# pico-v3.net
KiCad netlist of a schematic drawn in EAGLE
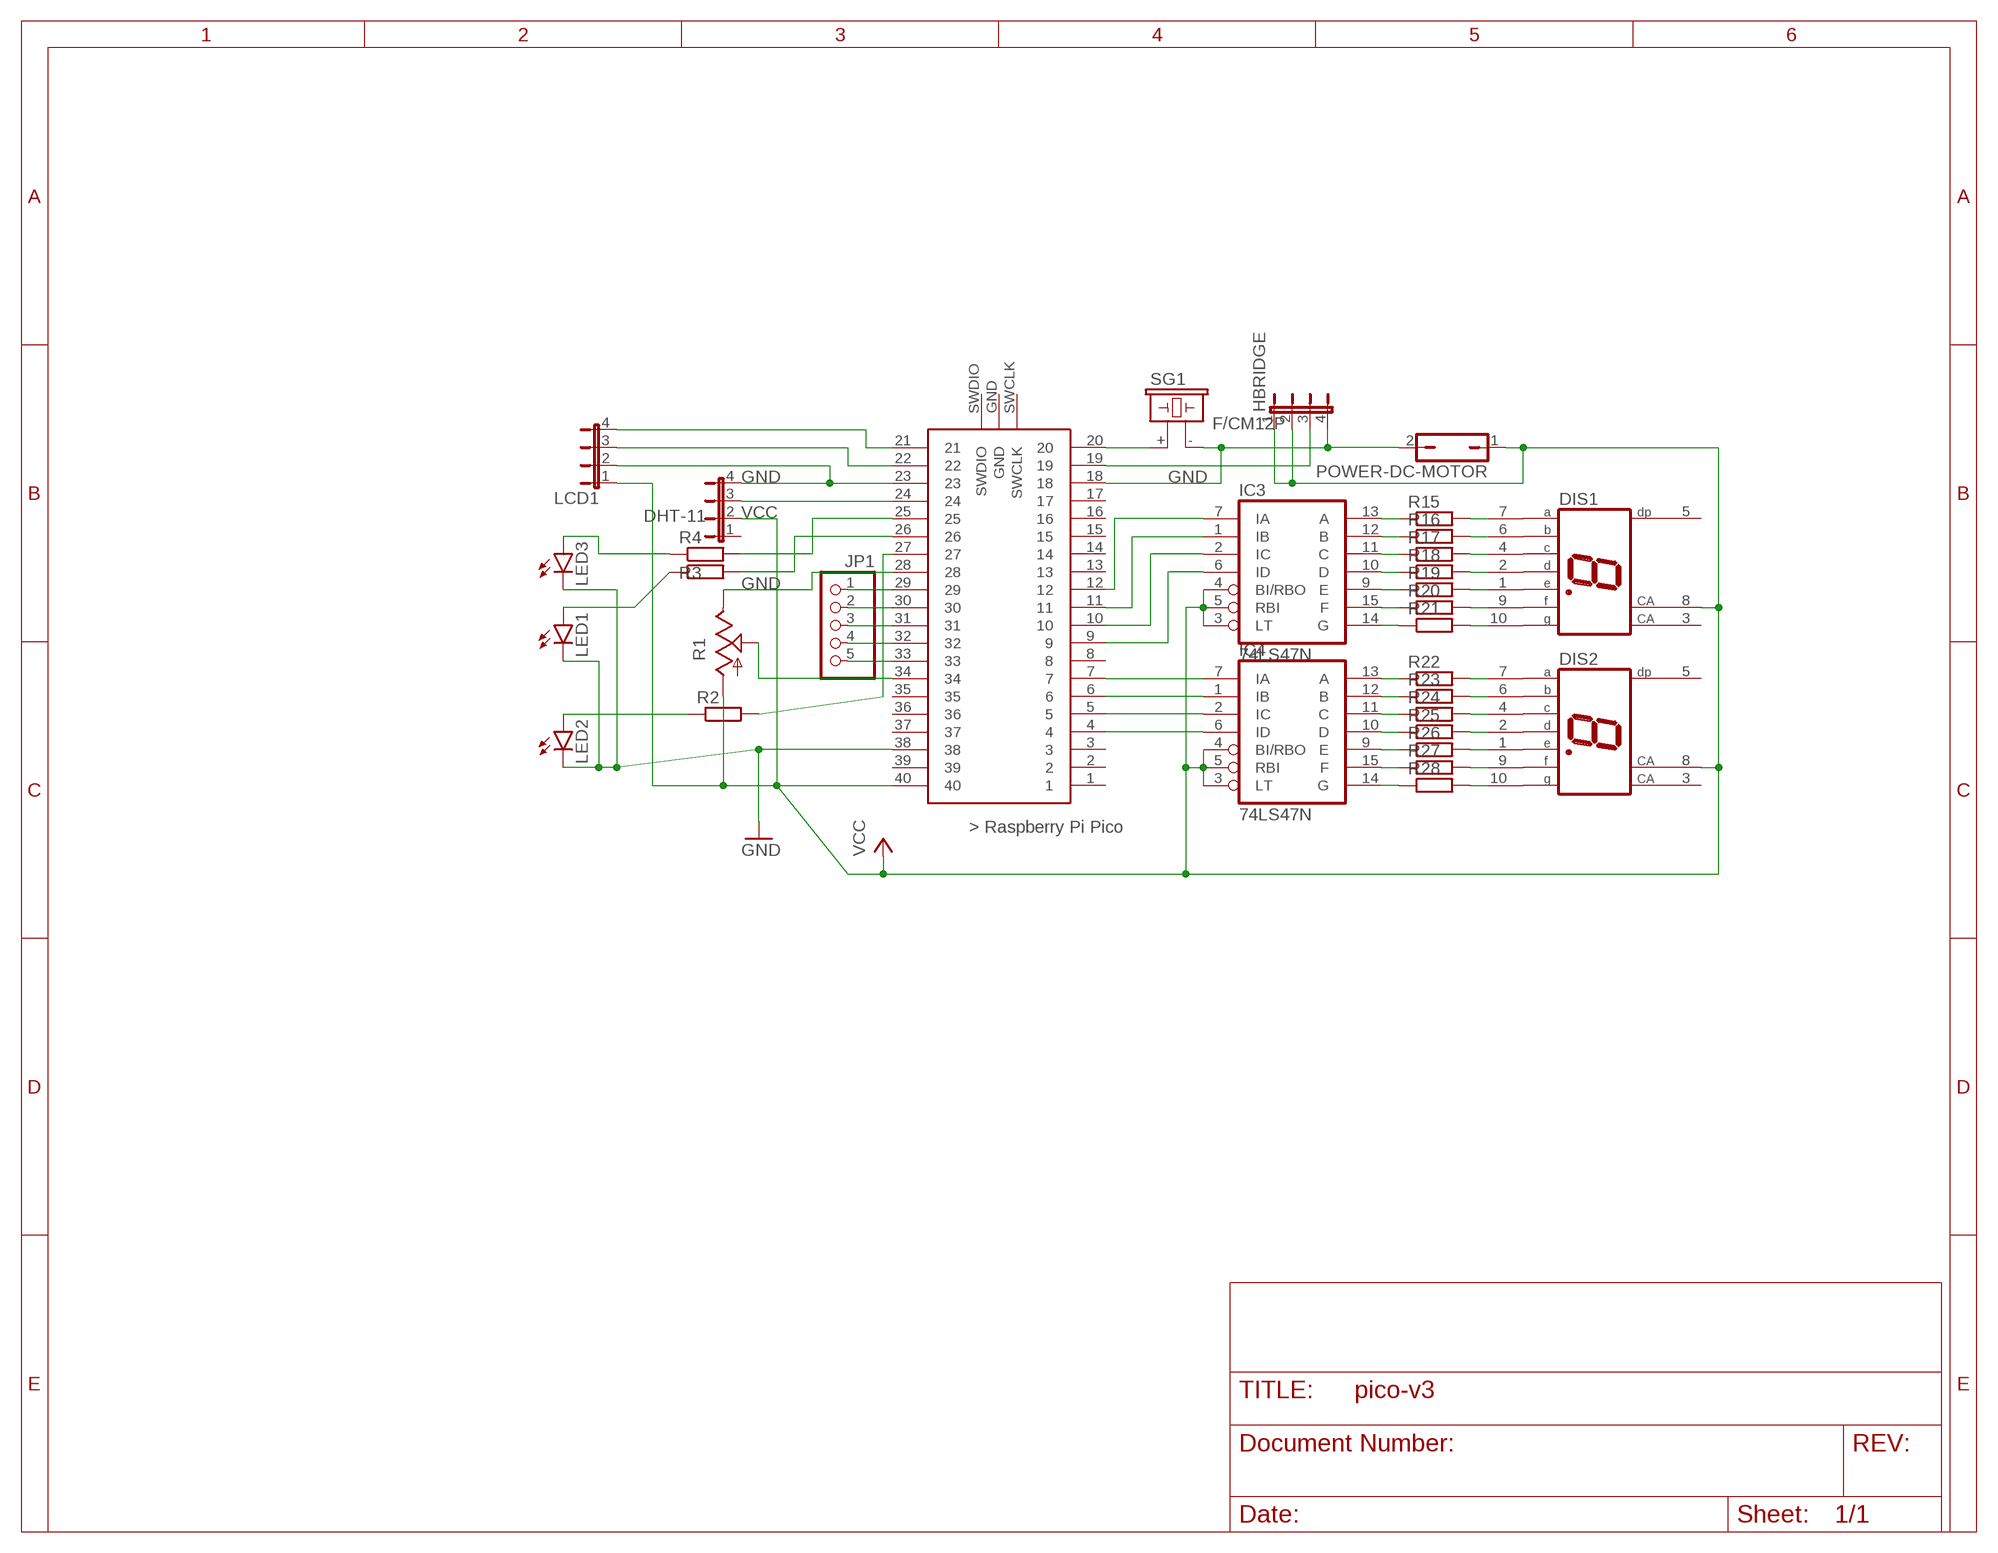
[diagram p0: schematic, sheet 1]

(export (version "E")
  (design (tool "Eeschema 10.0.6"))
  (components
    (comp (ref "DHT-11")
      (value "JP4E")
      (footprint "eagle-import:JP4")
      (libsource (lib "eagle-import") (part "JP4E"))
    )
    (comp (ref "DIS1")
      (value "HD-H101")
      (footprint "eagle-import:HDSP-M")
      (libsource (lib "eagle-import") (part "HD-H101"))
    )
    (comp (ref "DIS2")
      (value "HD-H101")
      (footprint "eagle-import:HDSP-M")
      (libsource (lib "eagle-import") (part "HD-H101"))
    )
    (comp (ref "HBRIDGE")
      (value "JP4E")
      (footprint "eagle-import:JP4")
      (libsource (lib "eagle-import") (part "JP4E"))
    )
    (comp (ref "IC3")
      (value "74LS47N")
      (footprint "eagle-import:DIL16")
      (libsource (lib "eagle-import") (part "7447NLS"))
    )
    (comp (ref "IC4")
      (value "74LS47N")
      (footprint "eagle-import:DIL16")
      (libsource (lib "eagle-import") (part "7447NLS"))
    )
    (comp (ref "JP1")
      (value "PINHD-1X5")
      (footprint "eagle-import:1X05")
      (libsource (lib "eagle-import") (part "PINHD-1X5"))
    )
    (comp (ref "LCD1")
      (value "JP4E")
      (footprint "eagle-import:JP4")
      (libsource (lib "eagle-import") (part "JP4E"))
    )
    (comp (ref "LED1")
      (value "LED5MM")
      (footprint "eagle-import:LED5MM")
      (libsource (lib "eagle-import") (part "LED5MM"))
    )
    (comp (ref "LED2")
      (value "LED5MM")
      (footprint "eagle-import:LED5MM")
      (libsource (lib "eagle-import") (part "LED5MM"))
    )
    (comp (ref "LED3")
      (value "LED5MM")
      (footprint "eagle-import:LED5MM")
      (libsource (lib "eagle-import") (part "LED5MM"))
    )
    (comp (ref "POWER-DC-MOTOR")
      (value "JP1Q")
      (footprint "eagle-import:JP1")
      (libsource (lib "eagle-import") (part "JP1Q"))
    )
    (comp (ref "R1")
      (value "TRIM_US-CA6V")
      (footprint "eagle-import:CA6V")
      (libsource (lib "eagle-import") (part "TRIM_US-CA6V"))
    )
    (comp (ref "R2")
      (value "R-EU_0207/10")
      (footprint "eagle-import:0207_10")
      (libsource (lib "eagle-import") (part "R-EU_0207/10"))
    )
    (comp (ref "R3")
      (value "R-EU_0207/10")
      (footprint "eagle-import:0207_10")
      (libsource (lib "eagle-import") (part "R-EU_0207/10"))
    )
    (comp (ref "R4")
      (value "R-EU_0207/10")
      (footprint "eagle-import:0207_10")
      (libsource (lib "eagle-import") (part "R-EU_0207/10"))
    )
    (comp (ref "R15")
      (value "R-EU_0207/12")
      (footprint "eagle-import:0207_12")
      (libsource (lib "eagle-import") (part "R-EU_0207/12"))
    )
    (comp (ref "R16")
      (value "R-EU_0207/12")
      (footprint "eagle-import:0207_12")
      (libsource (lib "eagle-import") (part "R-EU_0207/12"))
    )
    (comp (ref "R17")
      (value "R-EU_0207/12")
      (footprint "eagle-import:0207_12")
      (libsource (lib "eagle-import") (part "R-EU_0207/12"))
    )
    (comp (ref "R18")
      (value "R-EU_0207/12")
      (footprint "eagle-import:0207_12")
      (libsource (lib "eagle-import") (part "R-EU_0207/12"))
    )
    (comp (ref "R19")
      (value "R-EU_0207/12")
      (footprint "eagle-import:0207_12")
      (libsource (lib "eagle-import") (part "R-EU_0207/12"))
    )
    (comp (ref "R20")
      (value "R-EU_0207/12")
      (footprint "eagle-import:0207_12")
      (libsource (lib "eagle-import") (part "R-EU_0207/12"))
    )
    (comp (ref "R21")
      (value "R-EU_0207/12")
      (footprint "eagle-import:0207_12")
      (libsource (lib "eagle-import") (part "R-EU_0207/12"))
    )
    (comp (ref "R22")
      (value "R-EU_0207/12")
      (footprint "eagle-import:0207_12")
      (libsource (lib "eagle-import") (part "R-EU_0207/12"))
    )
    (comp (ref "R23")
      (value "R-EU_0207/12")
      (footprint "eagle-import:0207_12")
      (libsource (lib "eagle-import") (part "R-EU_0207/12"))
    )
    (comp (ref "R24")
      (value "R-EU_0207/12")
      (footprint "eagle-import:0207_12")
      (libsource (lib "eagle-import") (part "R-EU_0207/12"))
    )
    (comp (ref "R25")
      (value "R-EU_0207/12")
      (footprint "eagle-import:0207_12")
      (libsource (lib "eagle-import") (part "R-EU_0207/12"))
    )
    (comp (ref "R26")
      (value "R-EU_0207/12")
      (footprint "eagle-import:0207_12")
      (libsource (lib "eagle-import") (part "R-EU_0207/12"))
    )
    (comp (ref "R27")
      (value "R-EU_0207/12")
      (footprint "eagle-import:0207_12")
      (libsource (lib "eagle-import") (part "R-EU_0207/12"))
    )
    (comp (ref "R28")
      (value "R-EU_0207/12")
      (footprint "eagle-import:0207_12")
      (libsource (lib "eagle-import") (part "R-EU_0207/12"))
    )
    (comp (ref "SG1")
      (value "F/CM12P")
      (footprint "eagle-import:F_CM12P")
      (libsource (lib "eagle-import") (part "F/CM12P"))
    )
    (comp (ref "U$1")
      (value "RASPBERRY-PI-PICO_TH")
      (footprint "eagle-import:FT_RASPBERRY-PI-PICO_TH")
      (libsource (lib "eagle-import") (part "RASPBERRY-PI-PICO_TH"))
    )
  )
  (nets
    (net (code "1") (name "GND") (class "Default")
      (node (ref "DHT-11") (pin "4") (pinfunction "4_4") (pintype "passive"))
      (node (ref "HBRIDGE") (pin "4") (pinfunction "4_4") (pintype "passive"))
      (node (ref "LCD1") (pin "2") (pinfunction "2_2") (pintype "passive"))
      (node (ref "LED1") (pin "K") (pinfunction "C_K") (pintype "passive"))
      (node (ref "LED2") (pin "K") (pinfunction "C_K") (pintype "passive"))
      (node (ref "LED3") (pin "K") (pinfunction "C_K") (pintype "passive"))
      (node (ref "POWER-DC-MOTOR") (pin "2") (pinfunction "2_2") (pintype "passive"))
      (node (ref "R1") (pin "E") (pinfunction "E_E") (pintype "passive"))
      (node (ref "SG1") (pin "-") (pinfunction "2_-") (pintype "passive"))
      (node (ref "U$1") (pin "18") (pinfunction "18_18") (pintype "bidirectional"))
      (node (ref "U$1") (pin "23") (pinfunction "23_23") (pintype "bidirectional"))
      (node (ref "U$1") (pin "28") (pinfunction "28_28") (pintype "bidirectional"))
      (node (ref "U$1") (pin "38") (pinfunction "38_38") (pintype "bidirectional"))
    )
    (net (code "2") (name "Net-(DHT-11-Pad3)") (class "Default")
      (node (ref "DHT-11") (pin "3") (pinfunction "3_3") (pintype "passive"))
      (node (ref "U$1") (pin "24") (pinfunction "24_24") (pintype "bidirectional"))
    )
    (net (code "3") (name "Net-(DIS1-A)") (class "Default")
      (node (ref "DIS1") (pin "7") (pinfunction "A_7") (pintype "passive"))
      (node (ref "R15") (pin "2") (pinfunction "2_2") (pintype "passive"))
    )
    (net (code "4") (name "Net-(DIS1-B)") (class "Default")
      (node (ref "DIS1") (pin "6") (pinfunction "B_6") (pintype "passive"))
      (node (ref "R16") (pin "2") (pinfunction "2_2") (pintype "passive"))
    )
    (net (code "5") (name "Net-(DIS1-C)") (class "Default")
      (node (ref "DIS1") (pin "4") (pinfunction "C_4") (pintype "passive"))
      (node (ref "R17") (pin "2") (pinfunction "2_2") (pintype "passive"))
    )
    (net (code "6") (name "Net-(DIS1-D)") (class "Default")
      (node (ref "DIS1") (pin "2") (pinfunction "D_2") (pintype "passive"))
      (node (ref "R18") (pin "2") (pinfunction "2_2") (pintype "passive"))
    )
    (net (code "7") (name "Net-(DIS1-E)") (class "Default")
      (node (ref "DIS1") (pin "1") (pinfunction "E_1") (pintype "passive"))
      (node (ref "R19") (pin "2") (pinfunction "2_2") (pintype "passive"))
    )
    (net (code "8") (name "Net-(DIS1-F)") (class "Default")
      (node (ref "DIS1") (pin "9") (pinfunction "F_9") (pintype "passive"))
      (node (ref "R20") (pin "2") (pinfunction "2_2") (pintype "passive"))
    )
    (net (code "9") (name "Net-(DIS1-G)") (class "Default")
      (node (ref "DIS1") (pin "10") (pinfunction "G_10") (pintype "passive"))
      (node (ref "R21") (pin "2") (pinfunction "2_2") (pintype "passive"))
    )
    (net (code "10") (name "Net-(DIS2-A)") (class "Default")
      (node (ref "DIS2") (pin "7") (pinfunction "A_7") (pintype "passive"))
      (node (ref "R22") (pin "2") (pinfunction "2_2") (pintype "passive"))
    )
    (net (code "11") (name "Net-(DIS2-B)") (class "Default")
      (node (ref "DIS2") (pin "6") (pinfunction "B_6") (pintype "passive"))
      (node (ref "R23") (pin "2") (pinfunction "2_2") (pintype "passive"))
    )
    (net (code "12") (name "Net-(DIS2-C)") (class "Default")
      (node (ref "DIS2") (pin "4") (pinfunction "C_4") (pintype "passive"))
      (node (ref "R24") (pin "2") (pinfunction "2_2") (pintype "passive"))
    )
    (net (code "13") (name "Net-(DIS2-D)") (class "Default")
      (node (ref "DIS2") (pin "2") (pinfunction "D_2") (pintype "passive"))
      (node (ref "R25") (pin "2") (pinfunction "2_2") (pintype "passive"))
    )
    (net (code "14") (name "Net-(DIS2-E)") (class "Default")
      (node (ref "DIS2") (pin "1") (pinfunction "E_1") (pintype "passive"))
      (node (ref "R26") (pin "2") (pinfunction "2_2") (pintype "passive"))
    )
    (net (code "15") (name "Net-(DIS2-F)") (class "Default")
      (node (ref "DIS2") (pin "9") (pinfunction "F_9") (pintype "passive"))
      (node (ref "R27") (pin "2") (pinfunction "2_2") (pintype "passive"))
    )
    (net (code "16") (name "Net-(DIS2-G)") (class "Default")
      (node (ref "DIS2") (pin "10") (pinfunction "G_10") (pintype "passive"))
      (node (ref "R28") (pin "2") (pinfunction "2_2") (pintype "passive"))
    )
    (net (code "17") (name "Net-(HBRIDGE-Pad3)") (class "Default")
      (node (ref "HBRIDGE") (pin "3") (pinfunction "3_3") (pintype "passive"))
      (node (ref "U$1") (pin "19") (pinfunction "19_19") (pintype "bidirectional"))
    )
    (net (code "18") (name "Net-(IC3A-A)") (class "Default")
      (node (ref "IC3") (pin "13") (pinfunction "A_13") (pintype "output"))
      (node (ref "R15") (pin "1") (pinfunction "1_1") (pintype "passive"))
    )
    (net (code "19") (name "Net-(IC3A-B)") (class "Default")
      (node (ref "IC3") (pin "12") (pinfunction "B_12") (pintype "output"))
      (node (ref "R16") (pin "1") (pinfunction "1_1") (pintype "passive"))
    )
    (net (code "20") (name "Net-(IC3A-C)") (class "Default")
      (node (ref "IC3") (pin "11") (pinfunction "C_11") (pintype "output"))
      (node (ref "R17") (pin "1") (pinfunction "1_1") (pintype "passive"))
    )
    (net (code "21") (name "Net-(IC3A-D)") (class "Default")
      (node (ref "IC3") (pin "10") (pinfunction "D_10") (pintype "output"))
      (node (ref "R18") (pin "1") (pinfunction "1_1") (pintype "passive"))
    )
    (net (code "22") (name "Net-(IC3A-E)") (class "Default")
      (node (ref "IC3") (pin "9") (pinfunction "E_9") (pintype "output"))
      (node (ref "R19") (pin "1") (pinfunction "1_1") (pintype "passive"))
    )
    (net (code "23") (name "Net-(IC3A-F)") (class "Default")
      (node (ref "IC3") (pin "15") (pinfunction "F_15") (pintype "output"))
      (node (ref "R20") (pin "1") (pinfunction "1_1") (pintype "passive"))
    )
    (net (code "24") (name "Net-(IC3A-G)") (class "Default")
      (node (ref "IC3") (pin "14") (pinfunction "G_14") (pintype "output"))
      (node (ref "R21") (pin "1") (pinfunction "1_1") (pintype "passive"))
    )
    (net (code "25") (name "Net-(IC3A-IA)") (class "Default")
      (node (ref "IC3") (pin "7") (pinfunction "IA_7") (pintype "input"))
      (node (ref "U$1") (pin "12") (pinfunction "12_12") (pintype "bidirectional"))
    )
    (net (code "26") (name "Net-(IC3A-IB)") (class "Default")
      (node (ref "IC3") (pin "1") (pinfunction "IB_1") (pintype "input"))
      (node (ref "U$1") (pin "11") (pinfunction "11_11") (pintype "bidirectional"))
    )
    (net (code "27") (name "Net-(IC3A-IC)") (class "Default")
      (node (ref "IC3") (pin "2") (pinfunction "IC_2") (pintype "input"))
      (node (ref "U$1") (pin "10") (pinfunction "10_10") (pintype "bidirectional"))
    )
    (net (code "28") (name "Net-(IC3A-ID)") (class "Default")
      (node (ref "IC3") (pin "6") (pinfunction "ID_6") (pintype "input"))
      (node (ref "U$1") (pin "9") (pinfunction "9_9") (pintype "bidirectional"))
    )
    (net (code "29") (name "Net-(IC4A-A)") (class "Default")
      (node (ref "IC4") (pin "13") (pinfunction "A_13") (pintype "output"))
      (node (ref "R22") (pin "1") (pinfunction "1_1") (pintype "passive"))
    )
    (net (code "30") (name "Net-(IC4A-B)") (class "Default")
      (node (ref "IC4") (pin "12") (pinfunction "B_12") (pintype "output"))
      (node (ref "R23") (pin "1") (pinfunction "1_1") (pintype "passive"))
    )
    (net (code "31") (name "Net-(IC4A-C)") (class "Default")
      (node (ref "IC4") (pin "11") (pinfunction "C_11") (pintype "output"))
      (node (ref "R24") (pin "1") (pinfunction "1_1") (pintype "passive"))
    )
    (net (code "32") (name "Net-(IC4A-D)") (class "Default")
      (node (ref "IC4") (pin "10") (pinfunction "D_10") (pintype "output"))
      (node (ref "R25") (pin "1") (pinfunction "1_1") (pintype "passive"))
    )
    (net (code "33") (name "Net-(IC4A-E)") (class "Default")
      (node (ref "IC4") (pin "9") (pinfunction "E_9") (pintype "output"))
      (node (ref "R26") (pin "1") (pinfunction "1_1") (pintype "passive"))
    )
    (net (code "34") (name "Net-(IC4A-F)") (class "Default")
      (node (ref "IC4") (pin "15") (pinfunction "F_15") (pintype "output"))
      (node (ref "R27") (pin "1") (pinfunction "1_1") (pintype "passive"))
    )
    (net (code "35") (name "Net-(IC4A-G)") (class "Default")
      (node (ref "IC4") (pin "14") (pinfunction "G_14") (pintype "output"))
      (node (ref "R28") (pin "1") (pinfunction "1_1") (pintype "passive"))
    )
    (net (code "36") (name "Net-(IC4A-IA)") (class "Default")
      (node (ref "IC4") (pin "7") (pinfunction "IA_7") (pintype "input"))
      (node (ref "U$1") (pin "7") (pinfunction "7_7") (pintype "bidirectional"))
    )
    (net (code "37") (name "Net-(IC4A-IB)") (class "Default")
      (node (ref "IC4") (pin "1") (pinfunction "IB_1") (pintype "input"))
      (node (ref "U$1") (pin "6") (pinfunction "6_6") (pintype "bidirectional"))
    )
    (net (code "38") (name "Net-(IC4A-IC)") (class "Default")
      (node (ref "IC4") (pin "2") (pinfunction "IC_2") (pintype "input"))
      (node (ref "U$1") (pin "5") (pinfunction "5_5") (pintype "bidirectional"))
    )
    (net (code "39") (name "Net-(IC4A-ID)") (class "Default")
      (node (ref "IC4") (pin "6") (pinfunction "ID_6") (pintype "input"))
      (node (ref "U$1") (pin "4") (pinfunction "4_4") (pintype "bidirectional"))
    )
    (net (code "40") (name "Net-(JP1-Pad1)") (class "Default")
      (node (ref "JP1") (pin "1") (pinfunction "1_1") (pintype "passive"))
      (node (ref "U$1") (pin "29") (pinfunction "29_29") (pintype "bidirectional"))
    )
    (net (code "41") (name "Net-(JP1-Pad2)") (class "Default")
      (node (ref "JP1") (pin "2") (pinfunction "2_2") (pintype "passive"))
      (node (ref "U$1") (pin "30") (pinfunction "30_30") (pintype "bidirectional"))
    )
    (net (code "42") (name "Net-(JP1-Pad3)") (class "Default")
      (node (ref "JP1") (pin "3") (pinfunction "3_3") (pintype "passive"))
      (node (ref "U$1") (pin "31") (pinfunction "31_31") (pintype "bidirectional"))
    )
    (net (code "43") (name "Net-(JP1-Pad4)") (class "Default")
      (node (ref "JP1") (pin "4") (pinfunction "4_4") (pintype "passive"))
      (node (ref "U$1") (pin "32") (pinfunction "32_32") (pintype "bidirectional"))
    )
    (net (code "44") (name "Net-(JP1-Pad5)") (class "Default")
      (node (ref "JP1") (pin "5") (pinfunction "5_5") (pintype "passive"))
      (node (ref "U$1") (pin "33") (pinfunction "33_33") (pintype "bidirectional"))
    )
    (net (code "45") (name "Net-(LCD1-Pad3)") (class "Default")
      (node (ref "LCD1") (pin "3") (pinfunction "3_3") (pintype "passive"))
      (node (ref "U$1") (pin "22") (pinfunction "22_22") (pintype "bidirectional"))
    )
    (net (code "46") (name "Net-(LCD1-Pad4)") (class "Default")
      (node (ref "LCD1") (pin "4") (pinfunction "4_4") (pintype "passive"))
      (node (ref "U$1") (pin "21") (pinfunction "21_21") (pintype "bidirectional"))
    )
    (net (code "47") (name "Net-(LED1-PadA)") (class "Default")
      (node (ref "LED1") (pin "A") (pinfunction "A_A") (pintype "passive"))
      (node (ref "R3") (pin "1") (pinfunction "1_1") (pintype "passive"))
    )
    (net (code "48") (name "Net-(LED2-PadA)") (class "Default")
      (node (ref "LED2") (pin "A") (pinfunction "A_A") (pintype "passive"))
      (node (ref "R2") (pin "1") (pinfunction "1_1") (pintype "passive"))
    )
    (net (code "49") (name "Net-(LED3-PadA)") (class "Default")
      (node (ref "LED3") (pin "A") (pinfunction "A_A") (pintype "passive"))
      (node (ref "R4") (pin "1") (pinfunction "1_1") (pintype "passive"))
    )
    (net (code "50") (name "Net-(R1-PadS)") (class "Default")
      (node (ref "R1") (pin "S") (pinfunction "S_S") (pintype "passive"))
      (node (ref "U$1") (pin "34") (pinfunction "34_34") (pintype "bidirectional"))
    )
    (net (code "51") (name "Net-(R2-Pad2)") (class "Default")
      (node (ref "R2") (pin "2") (pinfunction "2_2") (pintype "passive"))
      (node (ref "U$1") (pin "27") (pinfunction "27_27") (pintype "bidirectional"))
    )
    (net (code "52") (name "Net-(R3-Pad2)") (class "Default")
      (node (ref "R3") (pin "2") (pinfunction "2_2") (pintype "passive"))
      (node (ref "U$1") (pin "26") (pinfunction "26_26") (pintype "bidirectional"))
    )
    (net (code "53") (name "Net-(R4-Pad2)") (class "Default")
      (node (ref "R4") (pin "2") (pinfunction "2_2") (pintype "passive"))
      (node (ref "U$1") (pin "25") (pinfunction "25_25") (pintype "bidirectional"))
    )
    (net (code "54") (name "Net-(SG1-1)") (class "Default")
      (node (ref "SG1") (pin "+") (pinfunction "1_+") (pintype "passive"))
      (node (ref "U$1") (pin "20") (pinfunction "20_20") (pintype "bidirectional"))
    )
    (net (code "55") (name "VCC") (class "Default")
      (node (ref "DHT-11") (pin "2") (pinfunction "2_2") (pintype "passive"))
      (node (ref "DIS1") (pin "8") (pinfunction "CA_8") (pintype "passive"))
      (node (ref "DIS2") (pin "8") (pinfunction "CA_8") (pintype "passive"))
      (node (ref "HBRIDGE") (pin "1") (pinfunction "1_1") (pintype "passive"))
      (node (ref "HBRIDGE") (pin "2") (pinfunction "2_2") (pintype "passive"))
      (node (ref "IC3") (pin "3") (pinfunction "LT_3") (pintype "input"))
      (node (ref "IC3") (pin "4") (pinfunction "BI/RBO_4") (pintype "input"))
      (node (ref "IC3") (pin "5") (pinfunction "RBI_5") (pintype "input"))
      (node (ref "IC4") (pin "3") (pinfunction "LT_3") (pintype "input"))
      (node (ref "IC4") (pin "4") (pinfunction "BI/RBO_4") (pintype "input"))
      (node (ref "IC4") (pin "5") (pinfunction "RBI_5") (pintype "input"))
      (node (ref "LCD1") (pin "1") (pinfunction "1_1") (pintype "passive"))
      (node (ref "POWER-DC-MOTOR") (pin "1") (pinfunction "1_1") (pintype "passive"))
      (node (ref "R1") (pin "A") (pinfunction "A_A") (pintype "passive"))
      (node (ref "U$1") (pin "40") (pinfunction "40_40") (pintype "bidirectional"))
    )
    (net (code "56") (name "unconnected-(DHT-11-Pad1)") (class "Default")
      (node (ref "DHT-11") (pin "1") (pinfunction "1_1") (pintype "passive"))
    )
    (net (code "57") (name "unconnected-(DIS1-CA-Pad3)") (class "Default")
      (node (ref "DIS1") (pin "3") (pinfunction "CA_3") (pintype "passive"))
    )
    (net (code "58") (name "unconnected-(DIS1-DP-Pad5)") (class "Default")
      (node (ref "DIS1") (pin "5") (pinfunction "DP_5") (pintype "passive"))
    )
    (net (code "59") (name "unconnected-(DIS2-CA-Pad3)") (class "Default")
      (node (ref "DIS2") (pin "3") (pinfunction "CA_3") (pintype "passive"))
    )
    (net (code "60") (name "unconnected-(DIS2-DP-Pad5)") (class "Default")
      (node (ref "DIS2") (pin "5") (pinfunction "DP_5") (pintype "passive"))
    )
    (net (code "61") (name "unconnected-(U$1-Pad1)") (class "Default")
      (node (ref "U$1") (pin "1") (pinfunction "1_1") (pintype "bidirectional"))
    )
    (net (code "62") (name "unconnected-(U$1-Pad2)") (class "Default")
      (node (ref "U$1") (pin "2") (pinfunction "2_2") (pintype "bidirectional"))
    )
    (net (code "63") (name "unconnected-(U$1-Pad3)") (class "Default")
      (node (ref "U$1") (pin "3") (pinfunction "3_3") (pintype "bidirectional"))
    )
    (net (code "64") (name "unconnected-(U$1-Pad8)") (class "Default")
      (node (ref "U$1") (pin "8") (pinfunction "8_8") (pintype "bidirectional"))
    )
    (net (code "65") (name "unconnected-(U$1-Pad13)") (class "Default")
      (node (ref "U$1") (pin "13") (pinfunction "13_13") (pintype "bidirectional"))
    )
    (net (code "66") (name "unconnected-(U$1-Pad14)") (class "Default")
      (node (ref "U$1") (pin "14") (pinfunction "14_14") (pintype "bidirectional"))
    )
    (net (code "67") (name "unconnected-(U$1-Pad15)") (class "Default")
      (node (ref "U$1") (pin "15") (pinfunction "15_15") (pintype "bidirectional"))
    )
    (net (code "68") (name "unconnected-(U$1-Pad16)") (class "Default")
      (node (ref "U$1") (pin "16") (pinfunction "16_16") (pintype "bidirectional"))
    )
    (net (code "69") (name "unconnected-(U$1-Pad17)") (class "Default")
      (node (ref "U$1") (pin "17") (pinfunction "17_17") (pintype "bidirectional"))
    )
    (net (code "70") (name "unconnected-(U$1-Pad35)") (class "Default")
      (node (ref "U$1") (pin "35") (pinfunction "35_35") (pintype "bidirectional"))
    )
    (net (code "71") (name "unconnected-(U$1-Pad36)") (class "Default")
      (node (ref "U$1") (pin "36") (pinfunction "36_36") (pintype "bidirectional"))
    )
    (net (code "72") (name "unconnected-(U$1-Pad37)") (class "Default")
      (node (ref "U$1") (pin "37") (pinfunction "37_37") (pintype "bidirectional"))
    )
    (net (code "73") (name "unconnected-(U$1-Pad39)") (class "Default")
      (node (ref "U$1") (pin "39") (pinfunction "39_39") (pintype "bidirectional"))
    )
    (net (code "74") (name "unconnected-(U$1-PadGND)") (class "Default")
      (node (ref "U$1") (pin "GND") (pinfunction "GND_GND") (pintype "bidirectional"))
    )
    (net (code "75") (name "unconnected-(U$1-PadSWCLK)") (class "Default")
      (node (ref "U$1") (pin "SWCLK") (pinfunction "SWCLK_SWCLK") (pintype "bidirectional"))
    )
    (net (code "76") (name "unconnected-(U$1-PadSWDIO)") (class "Default")
      (node (ref "U$1") (pin "SWDIO") (pinfunction "SWDIO_SWDIO") (pintype "bidirectional"))
    )
  )
)
